# Hirose64-ONIX-OE-Interposer.net
KiCad netlist of a schematic drawn in EAGLE
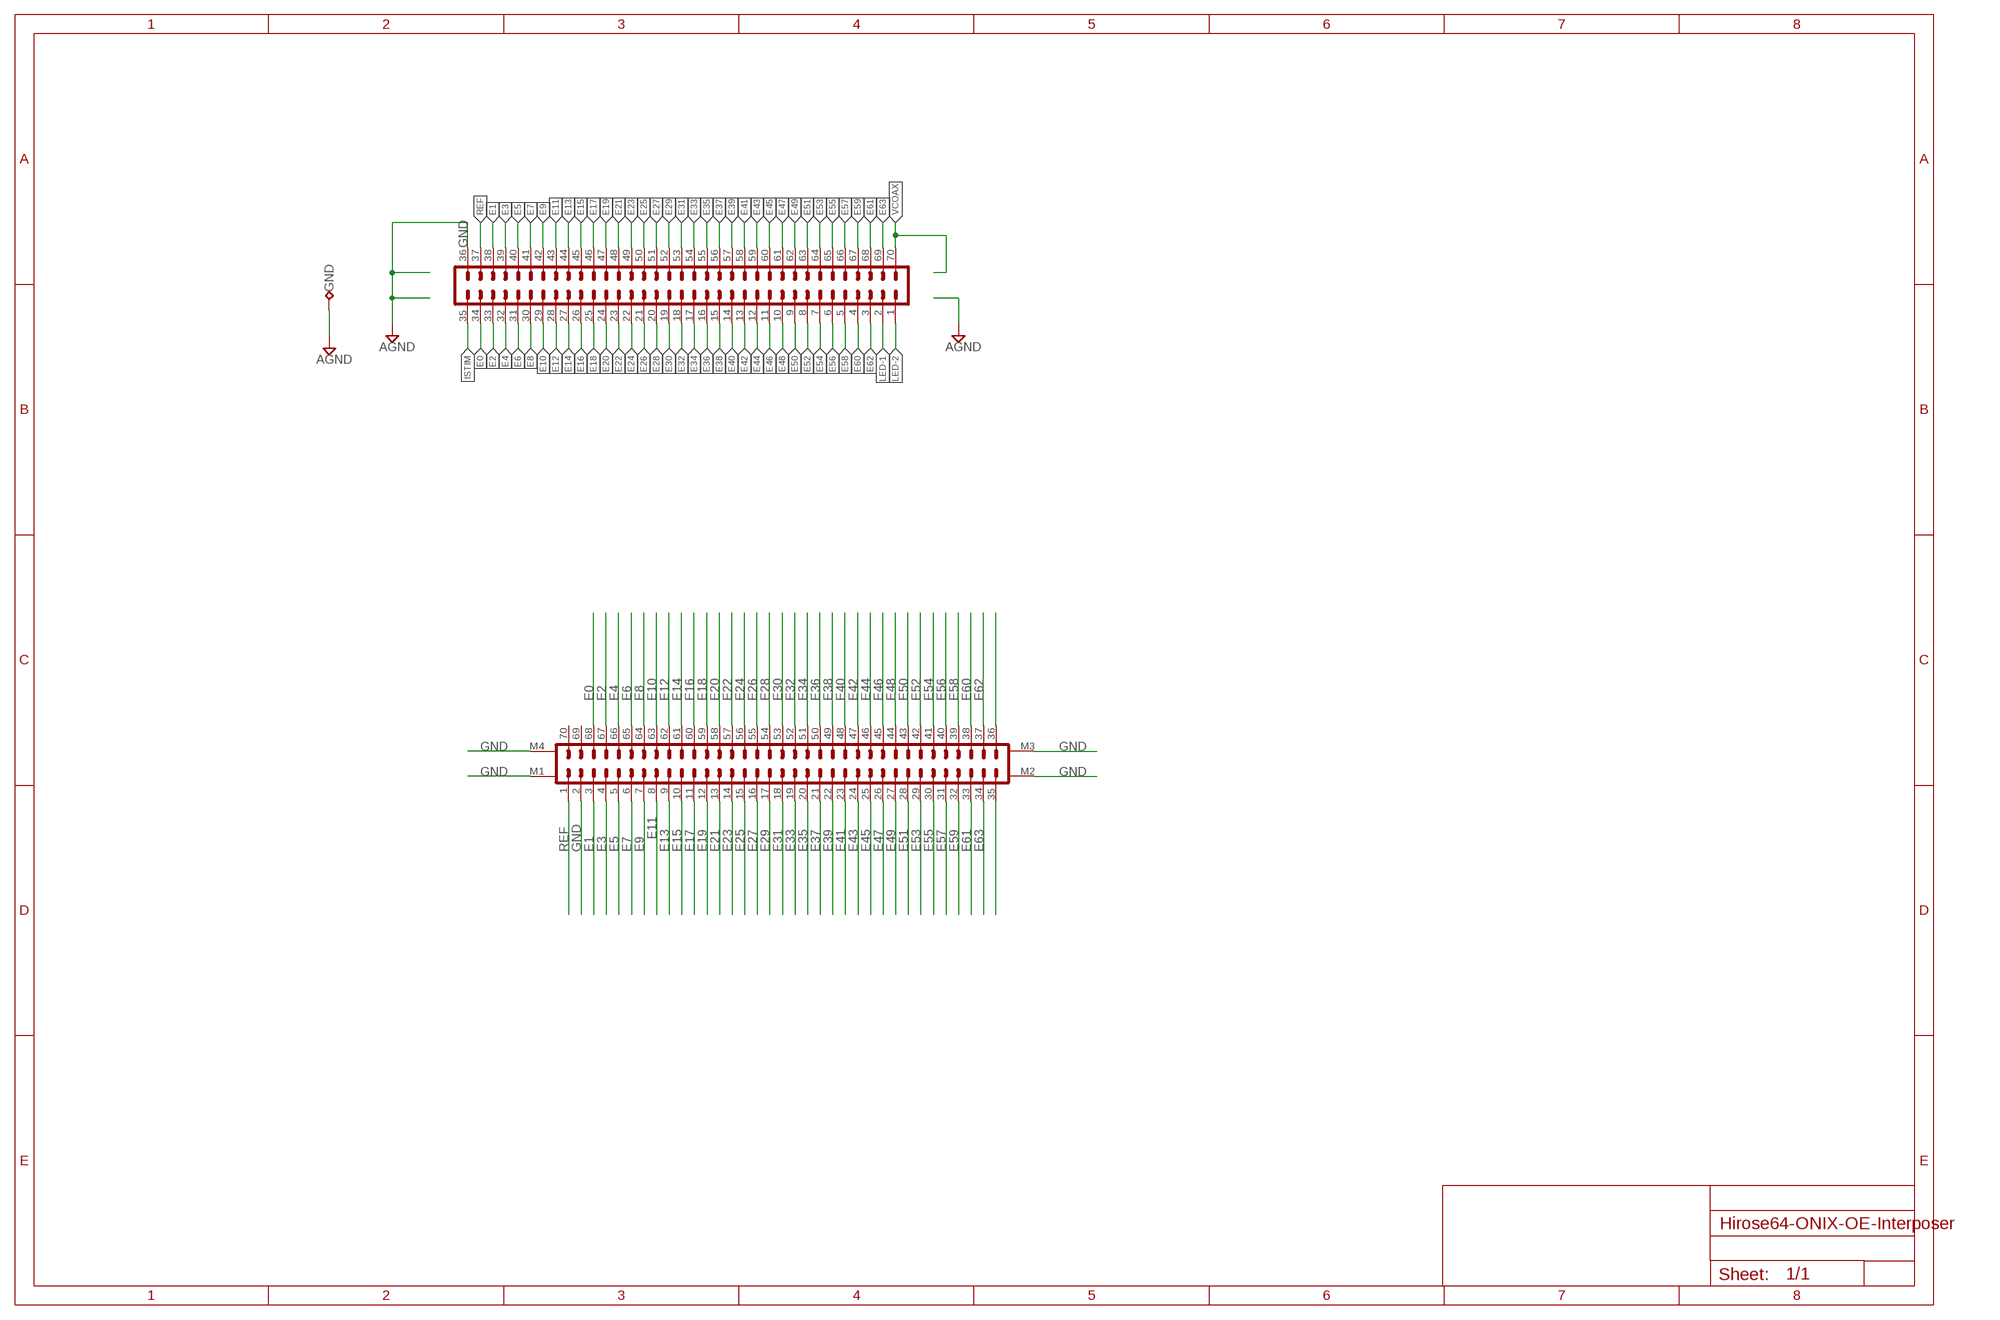
[diagram p0: schematic, sheet 1]

(export (version "E")
  (design (tool "Eeschema 10.0.6"))
  (components
    (comp (ref "GND")
      (value "GND")
      (footprint "eagle-import:TP07R")
      (libsource (lib "eagle-import") (part "TPTP07R"))
    )
    (comp (ref "J3")
      (value "DF40-REC")
      (footprint "eagle-import:DDF40-70REC-LRG")
      (libsource (lib "eagle-import") (part "PINHD-2X35_DF40REF-LRG"))
    )
    (comp (ref "J4")
      (value "DF40C-70DP-0.4V(51)")
      (footprint "eagle-import:DF40-70HEAD-LESS-SILK")
      (libsource (lib "eagle-import") (part "PINHD-2X35+4DF40-70HEAD-LESS-SILK"))
    )
  )
  (nets
    (net (code "1") (name "AGND") (class "Default")
      (node (ref "GND") (pin "TP") (pinfunction "TP_TP") (pintype "bidirectional"))
      (node (ref "J3") (pin "36") (pinfunction "36_36") (pintype "bidirectional"))
      (node (ref "J4") (pin "2") (pinfunction "2_2") (pintype "bidirectional"))
      (node (ref "J4") (pin "M1") (pinfunction "M1_M1") (pintype "bidirectional"))
      (node (ref "J4") (pin "M2") (pinfunction "M2_M2") (pintype "bidirectional"))
      (node (ref "J4") (pin "M3") (pinfunction "M3_M3") (pintype "bidirectional"))
      (node (ref "J4") (pin "M4") (pinfunction "M4_M4") (pintype "bidirectional"))
    )
    (net (code "2") (name "E0") (class "Default")
      (node (ref "J3") (pin "34") (pinfunction "34_34") (pintype "bidirectional"))
      (node (ref "J4") (pin "68") (pinfunction "68_68") (pintype "bidirectional"))
    )
    (net (code "3") (name "E1") (class "Default")
      (node (ref "J3") (pin "38") (pinfunction "38_38") (pintype "bidirectional"))
      (node (ref "J4") (pin "3") (pinfunction "3_3") (pintype "bidirectional"))
    )
    (net (code "4") (name "E2") (class "Default")
      (node (ref "J3") (pin "33") (pinfunction "33_33") (pintype "bidirectional"))
      (node (ref "J4") (pin "67") (pinfunction "67_67") (pintype "bidirectional"))
    )
    (net (code "5") (name "E3") (class "Default")
      (node (ref "J3") (pin "39") (pinfunction "39_39") (pintype "bidirectional"))
      (node (ref "J4") (pin "4") (pinfunction "4_4") (pintype "bidirectional"))
    )
    (net (code "6") (name "E4") (class "Default")
      (node (ref "J3") (pin "32") (pinfunction "32_32") (pintype "bidirectional"))
      (node (ref "J4") (pin "66") (pinfunction "66_66") (pintype "bidirectional"))
    )
    (net (code "7") (name "E5") (class "Default")
      (node (ref "J3") (pin "40") (pinfunction "40_40") (pintype "bidirectional"))
      (node (ref "J4") (pin "5") (pinfunction "5_5") (pintype "bidirectional"))
    )
    (net (code "8") (name "E6") (class "Default")
      (node (ref "J3") (pin "31") (pinfunction "31_31") (pintype "bidirectional"))
      (node (ref "J4") (pin "65") (pinfunction "65_65") (pintype "bidirectional"))
    )
    (net (code "9") (name "E7") (class "Default")
      (node (ref "J3") (pin "41") (pinfunction "41_41") (pintype "bidirectional"))
      (node (ref "J4") (pin "6") (pinfunction "6_6") (pintype "bidirectional"))
    )
    (net (code "10") (name "E8") (class "Default")
      (node (ref "J3") (pin "30") (pinfunction "30_30") (pintype "bidirectional"))
      (node (ref "J4") (pin "64") (pinfunction "64_64") (pintype "bidirectional"))
    )
    (net (code "11") (name "E9") (class "Default")
      (node (ref "J3") (pin "42") (pinfunction "42_42") (pintype "bidirectional"))
      (node (ref "J4") (pin "7") (pinfunction "7_7") (pintype "bidirectional"))
    )
    (net (code "12") (name "E10") (class "Default")
      (node (ref "J3") (pin "29") (pinfunction "29_29") (pintype "bidirectional"))
      (node (ref "J4") (pin "63") (pinfunction "63_63") (pintype "bidirectional"))
    )
    (net (code "13") (name "E11") (class "Default")
      (node (ref "J3") (pin "43") (pinfunction "43_43") (pintype "bidirectional"))
      (node (ref "J4") (pin "8") (pinfunction "8_8") (pintype "bidirectional"))
    )
    (net (code "14") (name "E12") (class "Default")
      (node (ref "J3") (pin "28") (pinfunction "28_28") (pintype "bidirectional"))
      (node (ref "J4") (pin "62") (pinfunction "62_62") (pintype "bidirectional"))
    )
    (net (code "15") (name "E13") (class "Default")
      (node (ref "J3") (pin "44") (pinfunction "44_44") (pintype "bidirectional"))
      (node (ref "J4") (pin "9") (pinfunction "9_9") (pintype "bidirectional"))
    )
    (net (code "16") (name "E14") (class "Default")
      (node (ref "J3") (pin "27") (pinfunction "27_27") (pintype "bidirectional"))
      (node (ref "J4") (pin "61") (pinfunction "61_61") (pintype "bidirectional"))
    )
    (net (code "17") (name "E15") (class "Default")
      (node (ref "J3") (pin "45") (pinfunction "45_45") (pintype "bidirectional"))
      (node (ref "J4") (pin "10") (pinfunction "10_10") (pintype "bidirectional"))
    )
    (net (code "18") (name "E16") (class "Default")
      (node (ref "J3") (pin "26") (pinfunction "26_26") (pintype "bidirectional"))
      (node (ref "J4") (pin "60") (pinfunction "60_60") (pintype "bidirectional"))
    )
    (net (code "19") (name "E17") (class "Default")
      (node (ref "J3") (pin "46") (pinfunction "46_46") (pintype "bidirectional"))
      (node (ref "J4") (pin "11") (pinfunction "11_11") (pintype "bidirectional"))
    )
    (net (code "20") (name "E18") (class "Default")
      (node (ref "J3") (pin "25") (pinfunction "25_25") (pintype "bidirectional"))
      (node (ref "J4") (pin "59") (pinfunction "59_59") (pintype "bidirectional"))
    )
    (net (code "21") (name "E19") (class "Default")
      (node (ref "J3") (pin "47") (pinfunction "47_47") (pintype "bidirectional"))
      (node (ref "J4") (pin "12") (pinfunction "12_12") (pintype "bidirectional"))
    )
    (net (code "22") (name "E20") (class "Default")
      (node (ref "J3") (pin "24") (pinfunction "24_24") (pintype "bidirectional"))
      (node (ref "J4") (pin "58") (pinfunction "58_58") (pintype "bidirectional"))
    )
    (net (code "23") (name "E21") (class "Default")
      (node (ref "J3") (pin "48") (pinfunction "48_48") (pintype "bidirectional"))
      (node (ref "J4") (pin "13") (pinfunction "13_13") (pintype "bidirectional"))
    )
    (net (code "24") (name "E22") (class "Default")
      (node (ref "J3") (pin "23") (pinfunction "23_23") (pintype "bidirectional"))
      (node (ref "J4") (pin "57") (pinfunction "57_57") (pintype "bidirectional"))
    )
    (net (code "25") (name "E23") (class "Default")
      (node (ref "J3") (pin "49") (pinfunction "49_49") (pintype "bidirectional"))
      (node (ref "J4") (pin "14") (pinfunction "14_14") (pintype "bidirectional"))
    )
    (net (code "26") (name "E24") (class "Default")
      (node (ref "J3") (pin "22") (pinfunction "22_22") (pintype "bidirectional"))
      (node (ref "J4") (pin "56") (pinfunction "56_56") (pintype "bidirectional"))
    )
    (net (code "27") (name "E25") (class "Default")
      (node (ref "J3") (pin "50") (pinfunction "50_50") (pintype "bidirectional"))
      (node (ref "J4") (pin "15") (pinfunction "15_15") (pintype "bidirectional"))
    )
    (net (code "28") (name "E26") (class "Default")
      (node (ref "J3") (pin "21") (pinfunction "21_21") (pintype "bidirectional"))
      (node (ref "J4") (pin "55") (pinfunction "55_55") (pintype "bidirectional"))
    )
    (net (code "29") (name "E27") (class "Default")
      (node (ref "J3") (pin "51") (pinfunction "51_51") (pintype "bidirectional"))
      (node (ref "J4") (pin "16") (pinfunction "16_16") (pintype "bidirectional"))
    )
    (net (code "30") (name "E28") (class "Default")
      (node (ref "J3") (pin "20") (pinfunction "20_20") (pintype "bidirectional"))
      (node (ref "J4") (pin "54") (pinfunction "54_54") (pintype "bidirectional"))
    )
    (net (code "31") (name "E29") (class "Default")
      (node (ref "J3") (pin "52") (pinfunction "52_52") (pintype "bidirectional"))
      (node (ref "J4") (pin "17") (pinfunction "17_17") (pintype "bidirectional"))
    )
    (net (code "32") (name "E30") (class "Default")
      (node (ref "J3") (pin "19") (pinfunction "19_19") (pintype "bidirectional"))
      (node (ref "J4") (pin "53") (pinfunction "53_53") (pintype "bidirectional"))
    )
    (net (code "33") (name "E31") (class "Default")
      (node (ref "J3") (pin "53") (pinfunction "53_53") (pintype "bidirectional"))
      (node (ref "J4") (pin "18") (pinfunction "18_18") (pintype "bidirectional"))
    )
    (net (code "34") (name "E32") (class "Default")
      (node (ref "J3") (pin "18") (pinfunction "18_18") (pintype "bidirectional"))
      (node (ref "J4") (pin "52") (pinfunction "52_52") (pintype "bidirectional"))
    )
    (net (code "35") (name "E33") (class "Default")
      (node (ref "J3") (pin "54") (pinfunction "54_54") (pintype "bidirectional"))
      (node (ref "J4") (pin "19") (pinfunction "19_19") (pintype "bidirectional"))
    )
    (net (code "36") (name "E34") (class "Default")
      (node (ref "J3") (pin "17") (pinfunction "17_17") (pintype "bidirectional"))
      (node (ref "J4") (pin "51") (pinfunction "51_51") (pintype "bidirectional"))
    )
    (net (code "37") (name "E35") (class "Default")
      (node (ref "J3") (pin "55") (pinfunction "55_55") (pintype "bidirectional"))
      (node (ref "J4") (pin "20") (pinfunction "20_20") (pintype "bidirectional"))
    )
    (net (code "38") (name "E36") (class "Default")
      (node (ref "J3") (pin "16") (pinfunction "16_16") (pintype "bidirectional"))
      (node (ref "J4") (pin "50") (pinfunction "50_50") (pintype "bidirectional"))
    )
    (net (code "39") (name "E37") (class "Default")
      (node (ref "J3") (pin "56") (pinfunction "56_56") (pintype "bidirectional"))
      (node (ref "J4") (pin "21") (pinfunction "21_21") (pintype "bidirectional"))
    )
    (net (code "40") (name "E38") (class "Default")
      (node (ref "J3") (pin "15") (pinfunction "15_15") (pintype "bidirectional"))
      (node (ref "J4") (pin "49") (pinfunction "49_49") (pintype "bidirectional"))
    )
    (net (code "41") (name "E39") (class "Default")
      (node (ref "J3") (pin "57") (pinfunction "57_57") (pintype "bidirectional"))
      (node (ref "J4") (pin "22") (pinfunction "22_22") (pintype "bidirectional"))
    )
    (net (code "42") (name "E40") (class "Default")
      (node (ref "J3") (pin "14") (pinfunction "14_14") (pintype "bidirectional"))
      (node (ref "J4") (pin "48") (pinfunction "48_48") (pintype "bidirectional"))
    )
    (net (code "43") (name "E41") (class "Default")
      (node (ref "J3") (pin "58") (pinfunction "58_58") (pintype "bidirectional"))
      (node (ref "J4") (pin "23") (pinfunction "23_23") (pintype "bidirectional"))
    )
    (net (code "44") (name "E42") (class "Default")
      (node (ref "J3") (pin "13") (pinfunction "13_13") (pintype "bidirectional"))
      (node (ref "J4") (pin "47") (pinfunction "47_47") (pintype "bidirectional"))
    )
    (net (code "45") (name "E43") (class "Default")
      (node (ref "J3") (pin "59") (pinfunction "59_59") (pintype "bidirectional"))
      (node (ref "J4") (pin "24") (pinfunction "24_24") (pintype "bidirectional"))
    )
    (net (code "46") (name "E44") (class "Default")
      (node (ref "J3") (pin "12") (pinfunction "12_12") (pintype "bidirectional"))
      (node (ref "J4") (pin "46") (pinfunction "46_46") (pintype "bidirectional"))
    )
    (net (code "47") (name "E45") (class "Default")
      (node (ref "J3") (pin "60") (pinfunction "60_60") (pintype "bidirectional"))
      (node (ref "J4") (pin "25") (pinfunction "25_25") (pintype "bidirectional"))
    )
    (net (code "48") (name "E46") (class "Default")
      (node (ref "J3") (pin "11") (pinfunction "11_11") (pintype "bidirectional"))
      (node (ref "J4") (pin "45") (pinfunction "45_45") (pintype "bidirectional"))
    )
    (net (code "49") (name "E47") (class "Default")
      (node (ref "J3") (pin "61") (pinfunction "61_61") (pintype "bidirectional"))
      (node (ref "J4") (pin "26") (pinfunction "26_26") (pintype "bidirectional"))
    )
    (net (code "50") (name "E48") (class "Default")
      (node (ref "J3") (pin "10") (pinfunction "10_10") (pintype "bidirectional"))
      (node (ref "J4") (pin "44") (pinfunction "44_44") (pintype "bidirectional"))
    )
    (net (code "51") (name "E49") (class "Default")
      (node (ref "J3") (pin "62") (pinfunction "62_62") (pintype "bidirectional"))
      (node (ref "J4") (pin "27") (pinfunction "27_27") (pintype "bidirectional"))
    )
    (net (code "52") (name "E50") (class "Default")
      (node (ref "J3") (pin "9") (pinfunction "9_9") (pintype "bidirectional"))
      (node (ref "J4") (pin "43") (pinfunction "43_43") (pintype "bidirectional"))
    )
    (net (code "53") (name "E51") (class "Default")
      (node (ref "J3") (pin "63") (pinfunction "63_63") (pintype "bidirectional"))
      (node (ref "J4") (pin "28") (pinfunction "28_28") (pintype "bidirectional"))
    )
    (net (code "54") (name "E52") (class "Default")
      (node (ref "J3") (pin "8") (pinfunction "8_8") (pintype "bidirectional"))
      (node (ref "J4") (pin "42") (pinfunction "42_42") (pintype "bidirectional"))
    )
    (net (code "55") (name "E53") (class "Default")
      (node (ref "J3") (pin "64") (pinfunction "64_64") (pintype "bidirectional"))
      (node (ref "J4") (pin "29") (pinfunction "29_29") (pintype "bidirectional"))
    )
    (net (code "56") (name "E54") (class "Default")
      (node (ref "J3") (pin "7") (pinfunction "7_7") (pintype "bidirectional"))
      (node (ref "J4") (pin "41") (pinfunction "41_41") (pintype "bidirectional"))
    )
    (net (code "57") (name "E55") (class "Default")
      (node (ref "J3") (pin "65") (pinfunction "65_65") (pintype "bidirectional"))
      (node (ref "J4") (pin "30") (pinfunction "30_30") (pintype "bidirectional"))
    )
    (net (code "58") (name "E56") (class "Default")
      (node (ref "J3") (pin "6") (pinfunction "6_6") (pintype "bidirectional"))
      (node (ref "J4") (pin "40") (pinfunction "40_40") (pintype "bidirectional"))
    )
    (net (code "59") (name "E57") (class "Default")
      (node (ref "J3") (pin "66") (pinfunction "66_66") (pintype "bidirectional"))
      (node (ref "J4") (pin "31") (pinfunction "31_31") (pintype "bidirectional"))
    )
    (net (code "60") (name "E58") (class "Default")
      (node (ref "J3") (pin "5") (pinfunction "5_5") (pintype "bidirectional"))
      (node (ref "J4") (pin "39") (pinfunction "39_39") (pintype "bidirectional"))
    )
    (net (code "61") (name "E59") (class "Default")
      (node (ref "J3") (pin "67") (pinfunction "67_67") (pintype "bidirectional"))
      (node (ref "J4") (pin "32") (pinfunction "32_32") (pintype "bidirectional"))
    )
    (net (code "62") (name "E60") (class "Default")
      (node (ref "J3") (pin "4") (pinfunction "4_4") (pintype "bidirectional"))
      (node (ref "J4") (pin "38") (pinfunction "38_38") (pintype "bidirectional"))
    )
    (net (code "63") (name "E61") (class "Default")
      (node (ref "J3") (pin "68") (pinfunction "68_68") (pintype "bidirectional"))
      (node (ref "J4") (pin "33") (pinfunction "33_33") (pintype "bidirectional"))
    )
    (net (code "64") (name "E62") (class "Default")
      (node (ref "J3") (pin "3") (pinfunction "3_3") (pintype "bidirectional"))
      (node (ref "J4") (pin "37") (pinfunction "37_37") (pintype "bidirectional"))
    )
    (net (code "65") (name "E63") (class "Default")
      (node (ref "J3") (pin "69") (pinfunction "69_69") (pintype "bidirectional"))
      (node (ref "J4") (pin "34") (pinfunction "34_34") (pintype "bidirectional"))
    )
    (net (code "66") (name "ISTIM") (class "Default")
      (node (ref "J3") (pin "35") (pinfunction "35_35") (pintype "bidirectional"))
    )
    (net (code "67") (name "LED-1") (class "Default")
      (node (ref "J3") (pin "2") (pinfunction "2_2") (pintype "bidirectional"))
    )
    (net (code "68") (name "LED-2") (class "Default")
      (node (ref "J3") (pin "1") (pinfunction "1_1") (pintype "bidirectional"))
    )
    (net (code "69") (name "REF") (class "Default")
      (node (ref "J3") (pin "37") (pinfunction "37_37") (pintype "bidirectional"))
      (node (ref "J4") (pin "1") (pinfunction "1_1") (pintype "bidirectional"))
    )
    (net (code "70") (name "VCOAX") (class "Default")
      (node (ref "J3") (pin "70") (pinfunction "70_70") (pintype "bidirectional"))
    )
    (net (code "71") (name "unconnected-(J4-Pad35)") (class "Default")
      (node (ref "J4") (pin "35") (pinfunction "35_35") (pintype "bidirectional"))
    )
    (net (code "72") (name "unconnected-(J4-Pad36)") (class "Default")
      (node (ref "J4") (pin "36") (pinfunction "36_36") (pintype "bidirectional"))
    )
    (net (code "73") (name "unconnected-(J4-Pad69)") (class "Default")
      (node (ref "J4") (pin "69") (pinfunction "69_69") (pintype "bidirectional"))
    )
    (net (code "74") (name "unconnected-(J4-Pad70)") (class "Default")
      (node (ref "J4") (pin "70") (pinfunction "70_70") (pintype "bidirectional"))
    )
  )
)
